# USB_OTG_HS.net
KiCad netlist of a schematic drawn in Altium Designer
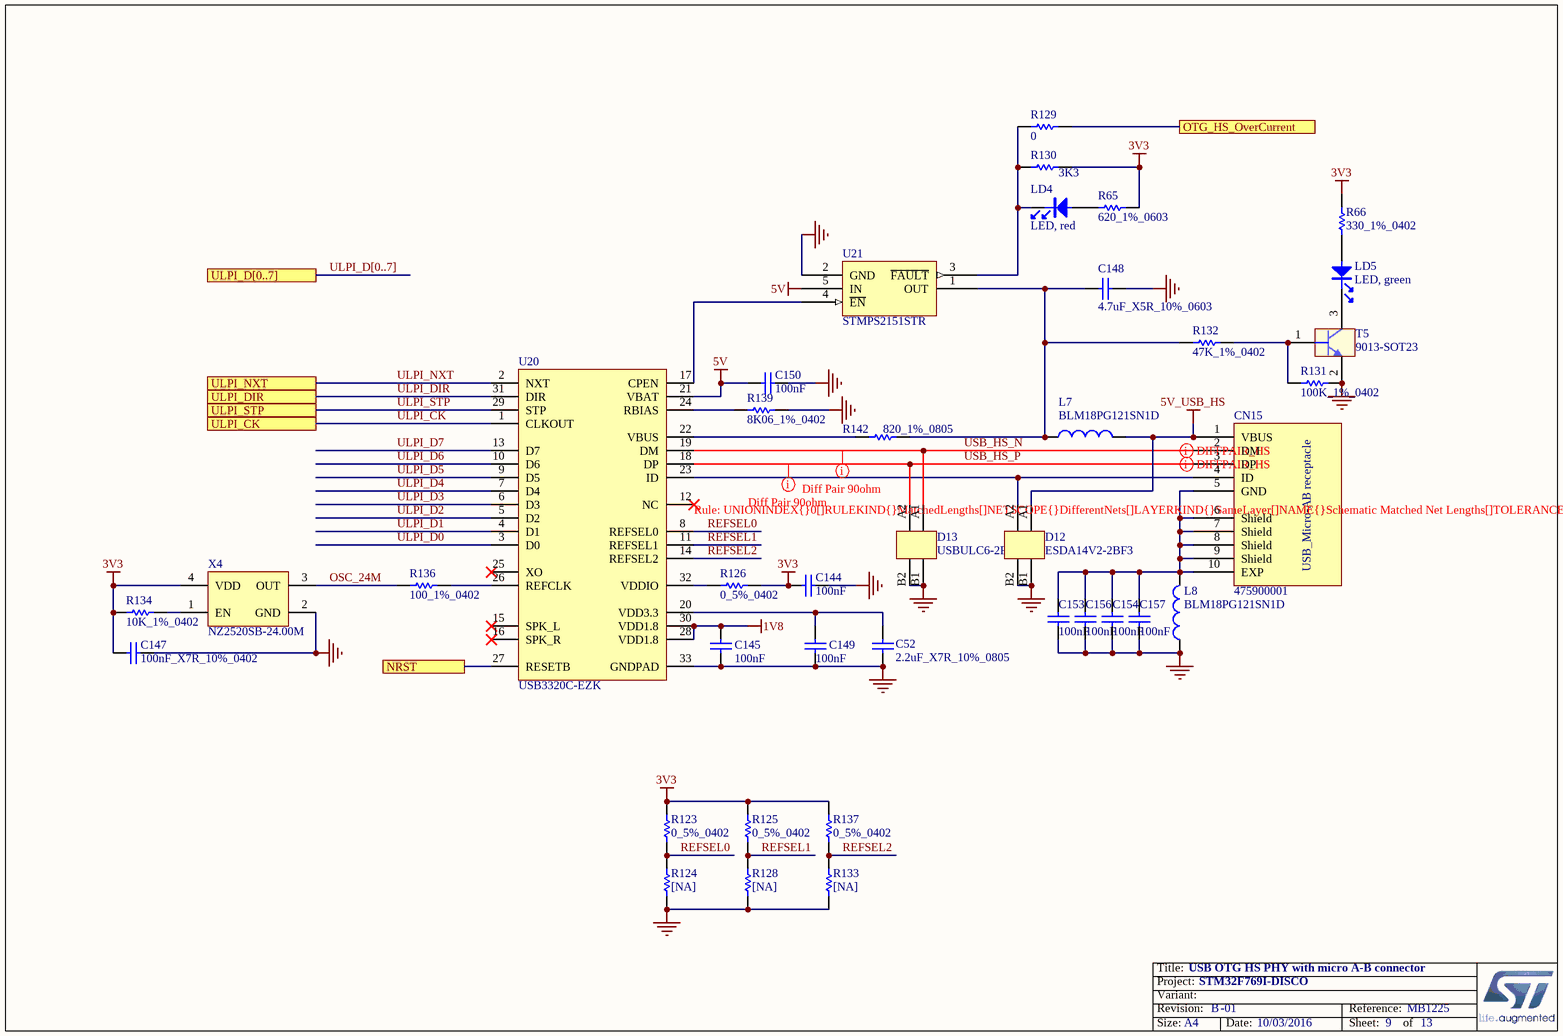
[diagram p0: USB_OTG_HS.SchDoc]

(export (version "E")
  (design (tool "Eeschema 10.0.6"))
  (components
    (comp (ref "C52")
      (value "2.2uF_X7R_10%_0805")
      (footprint "TAN-A")
      (description "Capacitor,2.2uF,16V, X7R,10%,0805,YAGEO")
      (libsource (lib "MCD_TOOLS") (part "Cap_2.2uF_X7R_10%_0805"))
    )
    (comp (ref "C144")
      (value "100nF")
      (footprint "0402C")
      (description "Capacitor,100nF,16V,X7R,10%,0402,YAGEO")
      (libsource (lib "MCD_TOOLS") (part "Cap_100nF_X7R_10%_0402"))
    )
    (comp (ref "C145")
      (value "100nF")
      (footprint "0402C")
      (description "Capacitor,100nF,16V,X7R,10%,0402,YAGEO")
      (libsource (lib "MCD_TOOLS") (part "Cap_100nF_X7R_10%_0402"))
    )
    (comp (ref "C147")
      (value "100nF_X7R_10%_0402")
      (footprint "0402C")
      (description "Capacitor,100nF,16V,X7R,10%,0402,YAGEO")
      (libsource (lib "MCD_TOOLS_CAPACITOR") (part "Cap_100nF_X7R_10%_0402"))
    )
    (comp (ref "C148")
      (value "4.7uF_X5R_10%_0603")
      (footprint "0603C")
      (description "Capacitor,4.7uF,16V, X5R,10%,0603,YAGEO")
      (libsource (lib "MCD_TOOLS") (part "Cap_4.7uF_X5R_10%_0603"))
    )
    (comp (ref "C149")
      (value "100nF")
      (footprint "0402C")
      (description "Capacitor,100nF,16V,X7R,10%,0402,YAGEO")
      (libsource (lib "MCD_TOOLS") (part "Cap_100nF_X7R_10%_0402"))
    )
    (comp (ref "C150")
      (value "100nF")
      (footprint "0402C")
      (description "Capacitor,100nF,16V,X7R,10%,0402,YAGEO")
      (libsource (lib "MCD_TOOLS") (part "Cap_100nF_X7R_10%_0402"))
    )
    (comp (ref "C153")
      (value "100nF")
      (footprint "0402C")
      (description "Capacitor,100nF,16V,X7R,10%,0402,YAGEO")
      (libsource (lib "MCD_TOOLS") (part "Cap_100nF_X7R_10%_0402"))
    )
    (comp (ref "C154")
      (value "100nF")
      (footprint "0402C")
      (description "Capacitor,100nF,16V,X7R,10%,0402,YAGEO")
      (libsource (lib "MCD_TOOLS") (part "Cap_100nF_X7R_10%_0402"))
    )
    (comp (ref "C156")
      (value "100nF")
      (footprint "0402C")
      (description "Capacitor,100nF,16V,X7R,10%,0402,YAGEO")
      (libsource (lib "MCD_TOOLS") (part "Cap_100nF_X7R_10%_0402"))
    )
    (comp (ref "C157")
      (value "100nF")
      (footprint "0402C")
      (description "Capacitor,100nF,16V,X7R,10%,0402,YAGEO")
      (libsource (lib "MCD_TOOLS") (part "Cap_100nF_X7R_10%_0402"))
    )
    (comp (ref "CN15")
      (value "475900001")
      (footprint "MOLEX_47590001")
      (description "USB-MICRO-AB, 47590-0001, SMT, MOLEX")
      (libsource (lib "MCD_TOOLS") (part "475900001"))
    )
    (comp (ref "D12")
      (value "ESDA14V2-2BF3")
      (footprint "BGA4_0R4_0R8X0R8")
      (description "Quad bidirectional Transil array for ESD protection")
      (libsource (lib "MCD_TOOLS_MISCELLANEOUS") (part "ESDA14V2-2BF3"))
    )
    (comp (ref "D13")
      (value "USBULC6-2F3")
      (footprint "BGA4_0R4_0R8X0R8")
      (description "2-line Transil, (TVS), ultralow capacitance protection for high speed USB")
      (libsource (lib "MCD_TOOLS_MISCELLANEOUS") (part "USBULC6-2F3"))
    )
    (comp (ref "L7")
      (value "BLM18PG121SN1D")
      (footprint "0603L")
      (description "Bead,120R,2A,0603,BLM18PG121SN1D,MURATA")
      (libsource (lib "MCD_TOOLS") (part "BEAD_120R_2A_0603"))
    )
    (comp (ref "L8")
      (value "BLM18PG121SN1D")
      (footprint "0603L")
      (description "Bead,120R,2A,0603,BLM18PG121SN1D,MURATA")
      (libsource (lib "MCD_TOOLS") (part "BEAD_120R_2A_0603"))
    )
    (comp (ref "LD4")
      (value "LED, red")
      (footprint "0603D")
      (description "LED, red, 0603")
      (libsource (lib "MCD_TOOLS") (part "LED_red"))
    )
    (comp (ref "LD5")
      (value "LED, green")
      (footprint "0603D")
      (description "LED, green, 0603")
      (libsource (lib "MCD_TOOLS") (part "LED_green"))
    )
    (comp (ref "R65")
      (value "620_1%_0603")
      (footprint "0603R")
      (description "Resistor,620,0603,1%,VISHAY")
      (libsource (lib "MCD_TOOLS") (part "Res_620_1%_0603"))
    )
    (comp (ref "R66")
      (value "330_1%_0402")
      (footprint "0402R")
      (description "Resistor,330,0402,1%,YAGEO")
      (libsource (lib "MCD_TOOLS") (part "Res_330_1%_0402"))
    )
    (comp (ref "R123")
      (value "0_5%_0402")
      (footprint "0402R")
      (description "Resistor,0,0402,5%,YAGEO")
      (libsource (lib "MCD_TOOLS") (part "Res_0_5%_0402"))
    )
    (comp (ref "R124")
      (value "[NA]")
      (footprint "0402R")
      (description "Resistor,[NA],0402")
      (libsource (lib "MCD_TOOLS") (part "Res_NA_0402"))
    )
    (comp (ref "R125")
      (value "0_5%_0402")
      (footprint "0402R")
      (description "Resistor,0,0402,5%,YAGEO")
      (libsource (lib "MCD_TOOLS") (part "Res_0_5%_0402"))
    )
    (comp (ref "R126")
      (value "0_5%_0402")
      (footprint "0402R")
      (description "Resistor,0,0402,5%,YAGEO")
      (libsource (lib "MCD_TOOLS") (part "Res_0_5%_0402"))
    )
    (comp (ref "R128")
      (value "[NA]")
      (footprint "0402R")
      (description "Resistor,[NA],0402")
      (libsource (lib "MCD_TOOLS") (part "Res_NA_0402"))
    )
    (comp (ref "R129")
      (value "0")
      (footprint "0402R")
      (description "Resistor,0,0402,5%,YAGEO")
      (libsource (lib "MCD_TOOLS") (part "Res_0_5%_0402"))
    )
    (comp (ref "R130")
      (value "3K3")
      (footprint "0402R")
      (description "Resistor,3K3,0402,1%,YAGEO")
      (libsource (lib "MCD_TOOLS") (part "Res_3K3_1%_0402"))
    )
    (comp (ref "R131")
      (value "100K_1%_0402")
      (footprint "0402R")
      (description "Resistor,100K,0402,1%,YAGEO")
      (libsource (lib "MCD_TOOLS_RESISTOR") (part "Res_100K_1%_0402"))
    )
    (comp (ref "R132")
      (value "47K_1%_0402")
      (footprint "0402R")
      (description "Resistor,47K,0402,1%,YAGEO")
      (libsource (lib "MCD_TOOLS") (part "Res_47K_1%_0402"))
    )
    (comp (ref "R133")
      (value "[NA]")
      (footprint "0402R")
      (description "Resistor,[NA],0402")
      (libsource (lib "MCD_TOOLS") (part "Res_NA_0402"))
    )
    (comp (ref "R134")
      (value "10K_1%_0402")
      (footprint "0402R")
      (description "Resistor,10K,0402,1%,YAGEO")
      (libsource (lib "MCD_TOOLS") (part "Res_10K_1%_0402"))
    )
    (comp (ref "R136")
      (value "100_1%_0402")
      (footprint "0402R")
      (description "Resistor,100,0402,1%,YAGEO")
      (libsource (lib "MCD_TOOLS") (part "Res_100_1%_0402"))
    )
    (comp (ref "R137")
      (value "0_5%_0402")
      (footprint "0402R")
      (description "Resistor,0,0402,5%,YAGEO")
      (libsource (lib "MCD_TOOLS") (part "Res_0_5%_0402"))
    )
    (comp (ref "R139")
      (value "8K06_1%_0402")
      (footprint "0402R")
      (description "Resistor,8K06,0402,1%,YAGEO")
      (libsource (lib "MCD_TOOLS") (part "Res_8K06_1%_0402"))
    )
    (comp (ref "R142")
      (value "820_1%_0805")
      (footprint "0805R")
      (description "Resistor,820,0805,1%,YAGEO")
      (libsource (lib "MCD_TOOLS") (part "Res_820_1%_0805"))
    )
    (comp (ref "T5")
      (value "9013-SOT23")
      (footprint "SOT-23")
      (description "NPN Bipolar Transistor")
      (libsource (lib "MCD_TOOLS_MISCELLANEOUS") (part "9013-SOT23"))
    )
    (comp (ref "U20")
      (value "USB3320C-EZK")
      (footprint "QFN32_0R5_5X5")
      (description "USB3320C,  Hi-Speed USB Host, Device or OTG PHY with ULPI Low Pin Interface")
      (fields (field (name "PROVIDED") "Sub Co"))
      (libsource (lib "MCD_TOOLS_MISCELLANEOUS") (part "USB3320C-EZK"))
    )
    (comp (ref "U21")
      (value "STMPS2151STR")
      (footprint "SOT23-5")
      (description "Enhanced single channel power switches")
      (libsource (lib "MCD_TOOLS_MISCELLANEOUS") (part "STMPS2151STR"))
    )
    (comp (ref "X4")
      (value "NZ2520SB-24.00M")
      (footprint "OSC_4SM_2R5X2")
      (description "Oscillator 24.00Mhz, -+50PPM, 3.3V, Temp -55 to +125°C")
      (libsource (lib "MCD_TOOLS_MISCELLANEOUS") (part "OSC_24M_NZ2520SB"))
    )
  )
  (nets
    (net (code "1") (name "/NRST") (class "Default")
      (node (ref "U20") (pin "27") (pinfunction "RESETB_27") (pintype "passive"))
    )
    (net (code "2") (name "/OSC_24M") (class "Default")
      (node (ref "R136") (pin "1") (pinfunction "1_1") (pintype "passive"))
      (node (ref "X4") (pin "3") (pinfunction "OUT_3") (pintype "passive"))
    )
    (net (code "3") (name "/OTG_HS_OverCurrent") (class "Default")
      (node (ref "R129") (pin "2") (pinfunction "2_2") (pintype "passive"))
    )
    (net (code "4") (name "/REFSEL0") (class "Default")
      (node (ref "R123") (pin "1") (pinfunction "1_1") (pintype "passive"))
      (node (ref "R124") (pin "2") (pinfunction "2_2") (pintype "passive"))
      (node (ref "U20") (pin "8") (pinfunction "REFSEL0_8") (pintype "passive"))
    )
    (net (code "5") (name "/REFSEL1") (class "Default")
      (node (ref "R125") (pin "1") (pinfunction "1_1") (pintype "passive"))
      (node (ref "R128") (pin "2") (pinfunction "2_2") (pintype "passive"))
      (node (ref "U20") (pin "11") (pinfunction "REFSEL1_11") (pintype "passive"))
    )
    (net (code "6") (name "/REFSEL2") (class "Default")
      (node (ref "R133") (pin "2") (pinfunction "2_2") (pintype "passive"))
      (node (ref "R137") (pin "1") (pinfunction "1_1") (pintype "passive"))
      (node (ref "U20") (pin "14") (pinfunction "REFSEL2_14") (pintype "passive"))
    )
    (net (code "7") (name "/ULPI_CK") (class "Default")
      (node (ref "U20") (pin "1") (pinfunction "CLKOUT_1") (pintype "passive"))
    )
    (net (code "8") (name "/ULPI_D0") (class "Default")
      (node (ref "U20") (pin "3") (pinfunction "D0_3") (pintype "passive"))
    )
    (net (code "9") (name "/ULPI_D1") (class "Default")
      (node (ref "U20") (pin "4") (pinfunction "D1_4") (pintype "passive"))
    )
    (net (code "10") (name "/ULPI_D2") (class "Default")
      (node (ref "U20") (pin "5") (pinfunction "D2_5") (pintype "passive"))
    )
    (net (code "11") (name "/ULPI_D3") (class "Default")
      (node (ref "U20") (pin "6") (pinfunction "D3_6") (pintype "passive"))
    )
    (net (code "12") (name "/ULPI_D4") (class "Default")
      (node (ref "U20") (pin "7") (pinfunction "D4_7") (pintype "passive"))
    )
    (net (code "13") (name "/ULPI_D5") (class "Default")
      (node (ref "U20") (pin "9") (pinfunction "D5_9") (pintype "passive"))
    )
    (net (code "14") (name "/ULPI_D6") (class "Default")
      (node (ref "U20") (pin "10") (pinfunction "D6_10") (pintype "passive"))
    )
    (net (code "15") (name "/ULPI_D7") (class "Default")
      (node (ref "U20") (pin "13") (pinfunction "D7_13") (pintype "passive"))
    )
    (net (code "16") (name "/ULPI_DIR") (class "Default")
      (node (ref "U20") (pin "31") (pinfunction "DIR_31") (pintype "passive"))
    )
    (net (code "18") (name "/ULPI_NXT") (class "Default")
      (node (ref "U20") (pin "2") (pinfunction "NXT_2") (pintype "passive"))
    )
    (net (code "19") (name "/ULPI_STP") (class "Default")
      (node (ref "U20") (pin "29") (pinfunction "STP_29") (pintype "passive"))
    )
    (net (code "20") (name "/USB_HS_N") (class "Default")
      (node (ref "CN15") (pin "2") (pinfunction "DM_2") (pintype "passive"))
      (node (ref "D13") (pin "A1") (pintype "passive"))
      (node (ref "U20") (pin "19") (pinfunction "DM_19") (pintype "passive"))
    )
    (net (code "21") (name "/USB_HS_P") (class "Default")
      (node (ref "CN15") (pin "3") (pinfunction "DP_3") (pintype "passive"))
      (node (ref "D13") (pin "A2") (pintype "passive"))
      (node (ref "U20") (pin "18") (pinfunction "DP_18") (pintype "passive"))
    )
    (net (code "22") (name "1V8") (class "Default")
      (node (ref "C145") (pin "2") (pinfunction "2_2") (pintype "passive"))
      (node (ref "U20") (pin "28") (pinfunction "VDD1.8_28") (pintype "passive"))
      (node (ref "U20") (pin "30") (pinfunction "VDD1.8_30") (pintype "passive"))
    )
    (net (code "23") (name "3V3") (class "Default")
      (node (ref "C144") (pin "1") (pinfunction "1_1") (pintype "passive"))
      (node (ref "C147") (pin "1") (pinfunction "1_1") (pintype "passive"))
      (node (ref "R123") (pin "2") (pinfunction "2_2") (pintype "passive"))
      (node (ref "R125") (pin "2") (pinfunction "2_2") (pintype "passive"))
      (node (ref "R126") (pin "2") (pinfunction "2_2") (pintype "passive"))
      (node (ref "R130") (pin "1") (pinfunction "1_1") (pintype "passive"))
      (node (ref "R134") (pin "1") (pinfunction "1_1") (pintype "passive"))
      (node (ref "R137") (pin "2") (pinfunction "2_2") (pintype "passive"))
      (node (ref "R65") (pin "2") (pinfunction "2_2") (pintype "passive"))
      (node (ref "R66") (pin "2") (pinfunction "2_2") (pintype "passive"))
      (node (ref "X4") (pin "4") (pinfunction "VDD_4") (pintype "passive"))
    )
    (net (code "24") (name "5V") (class "Default")
      (node (ref "C150") (pin "1") (pinfunction "1_1") (pintype "passive"))
      (node (ref "U20") (pin "21") (pinfunction "VBAT_21") (pintype "passive"))
      (node (ref "U21") (pin "5") (pinfunction "IN_5") (pintype "passive"))
    )
    (net (code "25") (name "5V_USB_HS") (class "Default")
      (node (ref "CN15") (pin "1") (pinfunction "VBUS_1") (pintype "passive"))
      (node (ref "D12") (pin "A1") (pintype "passive"))
      (node (ref "L7") (pin "2") (pinfunction "2_2") (pintype "passive"))
    )
    (net (code "26") (name "GND") (class "Default")
      (node (ref "C144") (pin "2") (pinfunction "2_2") (pintype "passive"))
      (node (ref "C145") (pin "1") (pinfunction "1_1") (pintype "passive"))
      (node (ref "C147") (pin "2") (pinfunction "2_2") (pintype "passive"))
      (node (ref "C148") (pin "2") (pinfunction "2_2") (pintype "passive"))
      (node (ref "C149") (pin "1") (pinfunction "1_1") (pintype "passive"))
      (node (ref "C150") (pin "2") (pinfunction "2_2") (pintype "passive"))
      (node (ref "C153") (pin "1") (pinfunction "1_1") (pintype "passive"))
      (node (ref "C154") (pin "1") (pinfunction "1_1") (pintype "passive"))
      (node (ref "C156") (pin "1") (pinfunction "1_1") (pintype "passive"))
      (node (ref "C157") (pin "1") (pinfunction "1_1") (pintype "passive"))
      (node (ref "C52") (pin "1") (pinfunction "1_1") (pintype "passive"))
      (node (ref "D12") (pin "B1") (pintype "passive"))
      (node (ref "D12") (pin "B2") (pintype "passive"))
      (node (ref "D13") (pin "B1") (pintype "passive"))
      (node (ref "D13") (pin "B2") (pintype "passive"))
      (node (ref "L8") (pin "1") (pinfunction "1_1") (pintype "passive"))
      (node (ref "R124") (pin "1") (pinfunction "1_1") (pintype "passive"))
      (node (ref "R128") (pin "1") (pinfunction "1_1") (pintype "passive"))
      (node (ref "R131") (pin "2") (pinfunction "2_2") (pintype "passive"))
      (node (ref "R133") (pin "1") (pinfunction "1_1") (pintype "passive"))
      (node (ref "R139") (pin "2") (pinfunction "2_2") (pintype "passive"))
      (node (ref "T5") (pin "2") (pinfunction "E_2") (pintype "passive"))
      (node (ref "U20") (pin "33") (pinfunction "GNDPAD_33") (pintype "passive"))
      (node (ref "U21") (pin "2") (pinfunction "GND_2") (pintype "passive"))
      (node (ref "X4") (pin "2") (pinfunction "GND_2") (pintype "passive"))
    )
    (net (code "27") (name "Net-(CN15-EXP)") (class "Default")
      (node (ref "C153") (pin "2") (pinfunction "2_2") (pintype "passive"))
      (node (ref "C154") (pin "2") (pinfunction "2_2") (pintype "passive"))
      (node (ref "C156") (pin "2") (pinfunction "2_2") (pintype "passive"))
      (node (ref "C157") (pin "2") (pinfunction "2_2") (pintype "passive"))
      (node (ref "CN15") (pin "10") (pinfunction "EXP_10") (pintype "passive"))
      (node (ref "CN15") (pin "5") (pinfunction "GND_5") (pintype "passive"))
      (node (ref "CN15") (pin "6") (pinfunction "Shield_6") (pintype "passive"))
      (node (ref "CN15") (pin "7") (pinfunction "Shield_7") (pintype "passive"))
      (node (ref "CN15") (pin "8") (pinfunction "Shield_8") (pintype "passive"))
      (node (ref "CN15") (pin "9") (pinfunction "Shield_9") (pintype "passive"))
      (node (ref "L8") (pin "2") (pinfunction "2_2") (pintype "passive"))
    )
    (net (code "28") (name "Net-(CN15-ID)") (class "Default")
      (node (ref "CN15") (pin "4") (pinfunction "ID_4") (pintype "passive"))
      (node (ref "D12") (pin "A2") (pintype "passive"))
      (node (ref "U20") (pin "23") (pinfunction "ID_23") (pintype "passive"))
    )
    (net (code "29") (name "Net-(LD4-Pad1)") (class "Default")
      (node (ref "LD4") (pin "1") (pintype "passive"))
      (node (ref "R65") (pin "1") (pinfunction "1_1") (pintype "passive"))
    )
    (net (code "30") (name "Net-(LD5-Pad1)") (class "Default")
      (node (ref "LD5") (pin "1") (pintype "passive"))
      (node (ref "R66") (pin "1") (pinfunction "1_1") (pintype "passive"))
    )
    (net (code "31") (name "Net-(T5-B)") (class "Default")
      (node (ref "R131") (pin "1") (pinfunction "1_1") (pintype "passive"))
      (node (ref "R132") (pin "2") (pinfunction "2_2") (pintype "passive"))
      (node (ref "T5") (pin "1") (pinfunction "B_1") (pintype "passive"))
    )
    (net (code "32") (name "Net-(T5-C)") (class "Default")
      (node (ref "LD5") (pin "2") (pintype "passive"))
      (node (ref "T5") (pin "3") (pinfunction "C_3") (pintype "passive"))
    )
    (net (code "33") (name "Net-(U20-CPEN)") (class "Default")
      (node (ref "U20") (pin "17") (pinfunction "CPEN_17") (pintype "passive"))
      (node (ref "U21") (pin "4") (pinfunction "~{EN}_4") (pintype "input"))
    )
    (net (code "34") (name "Net-(U20-RBIAS)") (class "Default")
      (node (ref "R139") (pin "1") (pinfunction "1_1") (pintype "passive"))
      (node (ref "U20") (pin "24") (pinfunction "RBIAS_24") (pintype "passive"))
    )
    (net (code "35") (name "Net-(U20-REFCLK)") (class "Default")
      (node (ref "R136") (pin "2") (pinfunction "2_2") (pintype "passive"))
      (node (ref "U20") (pin "26") (pinfunction "REFCLK_26") (pintype "passive"))
    )
    (net (code "36") (name "Net-(U20-VBUS)") (class "Default")
      (node (ref "R142") (pin "1") (pinfunction "1_1") (pintype "passive"))
      (node (ref "U20") (pin "22") (pinfunction "VBUS_22") (pintype "passive"))
    )
    (net (code "37") (name "Net-(U20-VDD3.3)") (class "Default")
      (node (ref "C149") (pin "2") (pinfunction "2_2") (pintype "passive"))
      (node (ref "C52") (pin "2") (pinfunction "2_2") (pintype "passive"))
      (node (ref "U20") (pin "20") (pinfunction "VDD3.3_20") (pintype "passive"))
    )
    (net (code "38") (name "Net-(U20-VDDIO)") (class "Default")
      (node (ref "R126") (pin "1") (pinfunction "1_1") (pintype "passive"))
      (node (ref "U20") (pin "32") (pinfunction "VDDIO_32") (pintype "passive"))
    )
    (net (code "39") (name "Net-(U21-OUT)") (class "Default")
      (node (ref "C148") (pin "1") (pinfunction "1_1") (pintype "passive"))
      (node (ref "L7") (pin "1") (pinfunction "1_1") (pintype "passive"))
      (node (ref "R132") (pin "1") (pinfunction "1_1") (pintype "passive"))
      (node (ref "R142") (pin "2") (pinfunction "2_2") (pintype "passive"))
      (node (ref "U21") (pin "1") (pinfunction "OUT_1") (pintype "passive"))
    )
    (net (code "40") (name "Net-(U21-~{FAULT})") (class "Default")
      (node (ref "LD4") (pin "2") (pintype "passive"))
      (node (ref "R129") (pin "1") (pinfunction "1_1") (pintype "passive"))
      (node (ref "R130") (pin "2") (pinfunction "2_2") (pintype "passive"))
      (node (ref "U21") (pin "3") (pinfunction "~{FAULT}_3") (pintype "output"))
    )
    (net (code "41") (name "Net-(X4-EN)") (class "Default")
      (node (ref "R134") (pin "2") (pinfunction "2_2") (pintype "passive"))
      (node (ref "X4") (pin "1") (pinfunction "EN_1") (pintype "passive"))
    )
    (net (code "42") (name "unconnected-(U20-NC-Pad12)") (class "Default")
      (node (ref "U20") (pin "12") (pinfunction "NC_12") (pintype "passive+no_connect"))
    )
    (net (code "43") (name "unconnected-(U20-SPK_L-Pad15)") (class "Default")
      (node (ref "U20") (pin "15") (pinfunction "SPK_L_15") (pintype "passive+no_connect"))
    )
    (net (code "44") (name "unconnected-(U20-SPK_R-Pad16)") (class "Default")
      (node (ref "U20") (pin "16") (pinfunction "SPK_R_16") (pintype "passive+no_connect"))
    )
    (net (code "45") (name "unconnected-(U20-XO-Pad25)") (class "Default")
      (node (ref "U20") (pin "25") (pinfunction "XO_25") (pintype "passive+no_connect"))
    )
  )
)
